# 5_Jetson_Nano_P1.net
KiCad netlist of a schematic drawn in Altium Designer
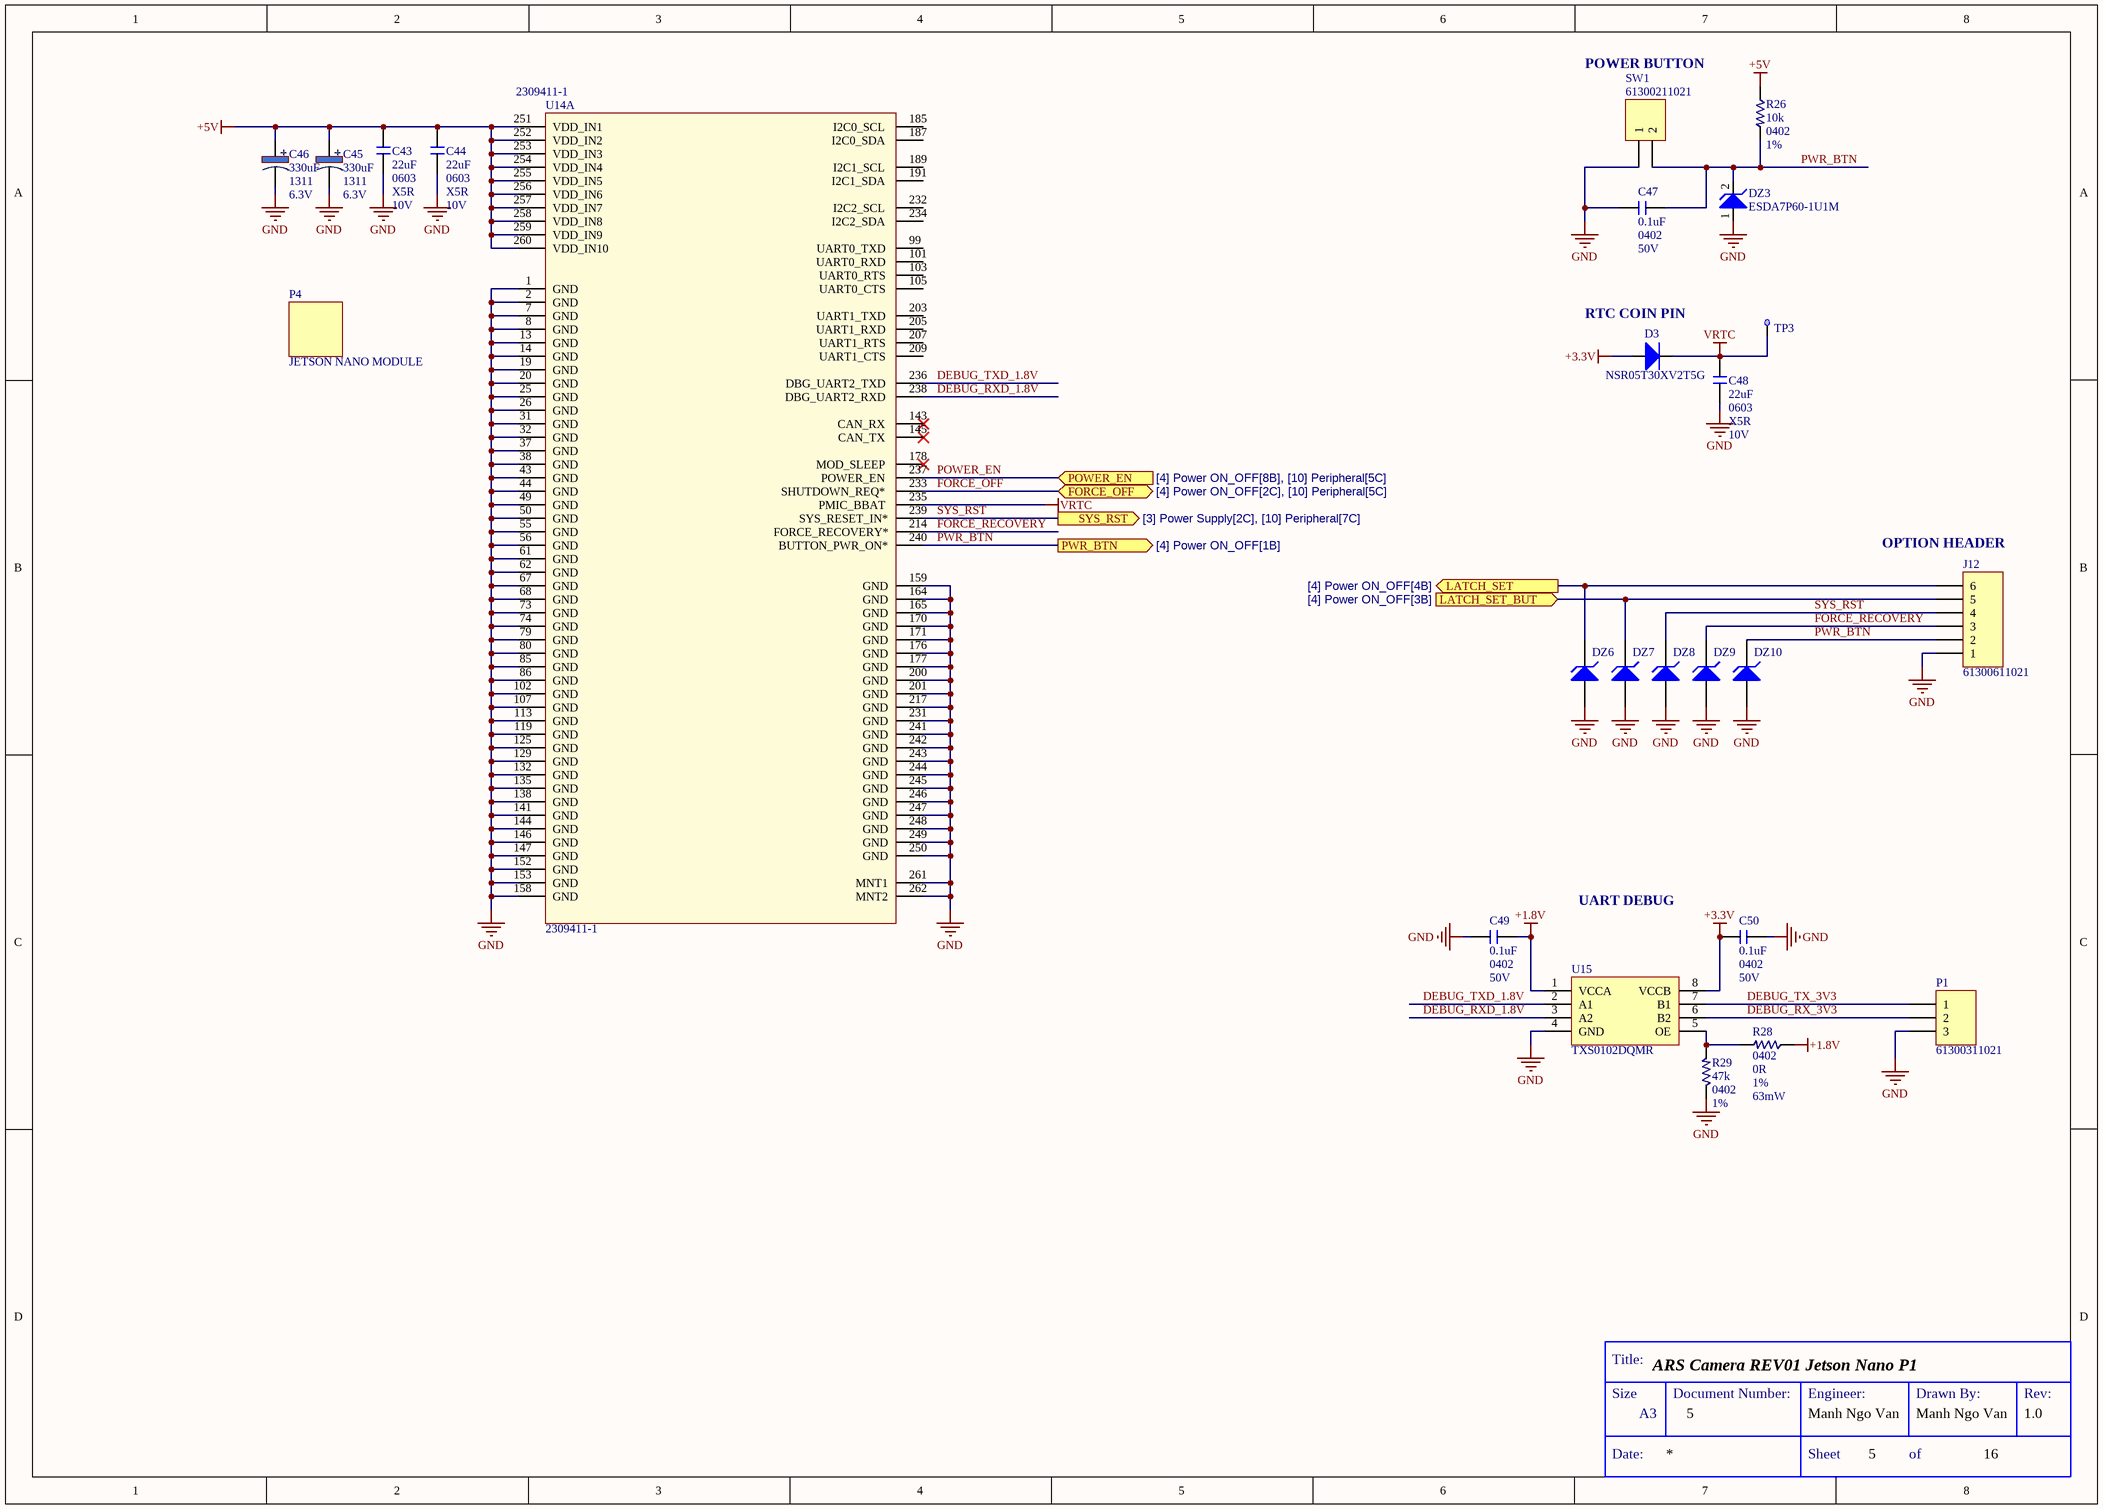
[diagram p0: [5] Jetson Nano P1.SchDoc]

(export (version "E")
  (design (tool "Eeschema 10.0.6"))
  (components
    (comp (ref "C43")
      (value "22uF")
      (footprint "C0603M")
      (description "CAP CER 22UF 10V X5R 0603")
      (fields
        (field (name "MANUFACTURER") "Samsung")
        (field (name "MANUFACTURER PART NUMBER") "CL10A226MP8NUNE")
        (field (name "CASE CODE (IMPERIAL)") "0603")
        (field (name "DIELECTRIC") "X5R")
        (field (name "VOLTAGE RATING") "10V")
      )
      (libsource (lib "CommonLib") (part "CAP_CER"))
    )
    (comp (ref "C44")
      (value "22uF")
      (footprint "C0603M")
      (description "CAP CER 22UF 10V X5R 0603")
      (fields
        (field (name "MANUFACTURER") "Samsung")
        (field (name "MANUFACTURER PART NUMBER") "CL10A226MP8NUNE")
        (field (name "CASE CODE (IMPERIAL)") "0603")
        (field (name "DIELECTRIC") "X5R")
        (field (name "VOLTAGE RATING") "10V")
      )
      (libsource (lib "CommonLib") (part "CAP_CER"))
    )
    (comp (ref "C45")
      (value "330uF")
      (footprint "CP_TANT_3528")
      (description "CAP TANT 330UF 20% 6.3V 1311")
      (fields
        (field (name "MANUFACTURER") "KEMET")
        (field (name "MANUFACTURER PART NUMBER") "T520B337M006ATE070")
        (field (name "CASE/PACKAGE") "1311")
        (field (name "VOLTAGE RATING") "6.3V")
      )
      (libsource (lib "CommonLib") (part "CAP_PL"))
    )
    (comp (ref "C46")
      (value "330uF")
      (footprint "CP_TANT_3528")
      (description "CAP TANT 330UF 20% 6.3V 1311")
      (fields
        (field (name "MANUFACTURER") "KEMET")
        (field (name "MANUFACTURER PART NUMBER") "T520B337M006ATE070")
        (field (name "CASE/PACKAGE") "1311")
        (field (name "VOLTAGE RATING") "6.3V")
      )
      (libsource (lib "CommonLib") (part "CAP_PL"))
    )
    (comp (ref "C47")
      (value "0.1uF")
      (footprint "C0402M")
      (description "CAP CER 0.1UF 50V X7R 0402")
      (fields
        (field (name "MANUFACTURER") "Murata")
        (field (name "MANUFACTURER PART NUMBER") "GRM155R71H104KE14D")
        (field (name "CASE/PACKAGE") "0402")
        (field (name "VOLTAGE") "50V")
      )
      (libsource (lib "CommonLib") (part "CAP_CER"))
    )
    (comp (ref "C48")
      (value "22uF")
      (footprint "C0603M")
      (description "CAP CER 22UF 10V X5R 0603")
      (fields
        (field (name "MANUFACTURER") "Samsung")
        (field (name "MANUFACTURER PART NUMBER") "CL10A226MP8NUNE")
        (field (name "CASE CODE (IMPERIAL)") "0603")
        (field (name "DIELECTRIC") "X5R")
        (field (name "VOLTAGE RATING") "10V")
      )
      (libsource (lib "CommonLib") (part "CAP_CER"))
    )
    (comp (ref "C49")
      (value "0.1uF")
      (footprint "C0402M")
      (description "CAP CER 0.1UF 50V X7R 0402")
      (fields
        (field (name "MANUFACTURER") "Murata")
        (field (name "MANUFACTURER PART NUMBER") "GRM155R71H104KE14D")
        (field (name "CASE/PACKAGE") "0402")
        (field (name "VOLTAGE") "50V")
      )
      (libsource (lib "CommonLib") (part "CAP_CER"))
    )
    (comp (ref "C50")
      (value "0.1uF")
      (footprint "C0402M")
      (description "CAP CER 0.1UF 50V X7R 0402")
      (fields
        (field (name "MANUFACTURER") "Murata")
        (field (name "MANUFACTURER PART NUMBER") "GRM155R71H104KE14D")
        (field (name "CASE/PACKAGE") "0402")
        (field (name "VOLTAGE") "50V")
      )
      (libsource (lib "CommonLib") (part "CAP_CER"))
    )
    (comp (ref "D3")
      (value "NSR05T30XV2T5G")
      (footprint "SODFL160X70-2N")
      (description "DIODE SCHOTTKY 30V 500MA SOD523")
      (fields (field (name "MANUFACTURER") "ON Semiconductor"))
      (libsource (lib "Altium_Library") (part "Diode"))
    )
    (comp (ref "DZ3")
      (value "ESDA7P60-1U1M")
      (footprint "DFN105P160X60-2N")
      (description "TVS DIODE 5V 11.6V 1610")
      (fields (field (name "MANUFACTURER") "STMicroelectronics"))
      (libsource (lib "Ikalogic_MotherBoard") (part "ESDA7P60-1U1M"))
    )
    (comp (ref "DZ6")
      (value "TPD1E10B06DPYR")
      (footprint "R0402M")
      (description "TVS DIODE 5.5V 14V 2X1SON")
      (fields (field (name "MANUFACTURER") "Texas Instruments"))
      (libsource (lib "CommonLib") (part "D Zener"))
    )
    (comp (ref "DZ7")
      (value "TPD1E10B06DPYR")
      (footprint "R0402M")
      (description "TVS DIODE 5.5V 14V 2X1SON")
      (fields (field (name "MANUFACTURER") "Texas Instruments"))
      (libsource (lib "CommonLib") (part "D Zener"))
    )
    (comp (ref "DZ8")
      (value "TPD1E10B06DPYR")
      (footprint "R0402M")
      (description "TVS DIODE 5.5V 14V 2X1SON")
      (fields (field (name "MANUFACTURER") "Texas Instruments"))
      (libsource (lib "CommonLib") (part "D Zener"))
    )
    (comp (ref "DZ9")
      (value "TPD1E10B06DPYR")
      (footprint "R0402M")
      (description "TVS DIODE 5.5V 14V 2X1SON")
      (fields (field (name "MANUFACTURER") "Texas Instruments"))
      (libsource (lib "CommonLib") (part "D Zener"))
    )
    (comp (ref "DZ10")
      (value "TPD1E10B06DPYR")
      (footprint "R0402M")
      (description "TVS DIODE 5.5V 14V 2X1SON")
      (fields (field (name "MANUFACTURER") "Texas Instruments"))
      (libsource (lib "CommonLib") (part "D Zener"))
    )
    (comp (ref "J12")
      (value "61300611021")
      (footprint "HDR1X6")
      (description "CONN HEADER R/A 6POS 2.54MM")
      (fields (field (name "MANUFACTURER") "Würth Elektronik GmbH"))
      (libsource (lib "3DAS_4Camera") (part "Header 6"))
    )
    (comp (ref "P1")
      (value "61300311021")
      (footprint "HDR1X3")
      (description "CONN HEADER R/A 3POS 2.54MM")
      (fields (field (name "MANUFACTURER") "Würth Elektronik GmbH"))
      (libsource (lib "Miscellaneous Connectors") (part "Header 3"))
    )
    (comp (ref "P4") (value "JETSON NANO MODULE") (libsource (lib "CommonLib") (part "ADDITION")))
    (comp (ref "R26")
      (value "10k")
      (footprint "R0402M")
      (description "RES SMD 10K OHM 1% 1/16W 0402")
      (fields
        (field (name "MANUFACTURER") "Yageo")
        (field (name "MANUFACTURER PART NUMBER") "RC0402FR-0710KL")
        (field (name "CASE CODE (IMPERIAL)") "0402")
        (field (name "TOLERANCE") "1%")
      )
      (libsource (lib "CommonLib") (part "RES_SMD"))
    )
    (comp (ref "R28")
      (value "RC0402FR-070RL")
      (footprint "R0402M")
      (description "RC Series 0402 0.063 W 0 Ohm Jumper Surface Mount Thick Film Chip Resistor")
      (fields
        (field (name "CASE CODE (IMPERIAL)") "0402")
        (field (name "RESISTANCE") "0R")
        (field (name "TOLERANCE") "1%")
        (field (name "MAX POWER DISSIPATION") "63mW")
      )
      (libsource (lib "CommonLib") (part "RES_SMD"))
    )
    (comp (ref "R29")
      (value "47k")
      (footprint "R0402M")
      (description "RES SMD 47K OHM 1% 1/16W 0402")
      (fields
        (field (name "MANUFACTURER") "Yageo")
        (field (name "MANUFACTURER PART NUMBER") "RC0402FR-0747KL")
        (field (name "CASE CODE (IMPERIAL)") "0402")
        (field (name "TOLERANCE") "1%")
      )
      (libsource (lib "CommonLib") (part "RES_SMD"))
    )
    (comp (ref "SW1")
      (value "61300211021")
      (footprint "HDR1X2")
      (description "CONN HEADER R/A 2POS 2.54MM")
      (fields (field (name "MANUFACTURER") "Würth Elektronik GmbH"))
      (libsource (lib "Miscellaneous Connectors") (part "Header 2"))
    )
    (comp (ref "TP3")
      (value "TP")
      (footprint "Test point")
      (description "TESTPOINT")
      (libsource (lib "CommonLib") (part "TestPoint"))
    )
    (comp (ref "U14")
      (value "2309411-1")
      (footprint "2309411-1")
      (description "DDR4 SODIMM 260P 8.0H STD")
      (fields
        (field (name "MANUFACTURER") "TE Connectivity")
        (field (name "SUPPLIER PART NUMBER 1") "2309411-1")
      )
      (libsource (lib "Nauvus") (part "Jetson Nano SODIMM"))
    )
    (comp (ref "U15")
      (value "TXS0102DQMR")
      (footprint "SON35P100X40-8N")
      (description "IC TRNSLTR BIDIRECTIONAL 8X2SON")
      (fields (field (name "MANUFACTURER") "Texas Instruments"))
      (libsource (lib "Nauvus") (part "TXS0102DQMR"))
    )
  )
  (nets
    (net (code "1") (name "+1.8V") (class "Default")
      (node (ref "C49") (pin "2") (pinfunction "2_2") (pintype "passive"))
      (node (ref "R28") (pin "2") (pinfunction "2_2") (pintype "passive"))
      (node (ref "U15") (pin "1") (pinfunction "VCCA_1") (pintype "passive"))
    )
    (net (code "2") (name "+3.3V") (class "Default")
      (node (ref "C50") (pin "2") (pinfunction "2_2") (pintype "passive"))
      (node (ref "D3") (pin "2") (pinfunction "A_2") (pintype "passive"))
      (node (ref "U15") (pin "8") (pinfunction "VCCB_8") (pintype "passive"))
    )
    (net (code "3") (name "+5V") (class "Default")
      (node (ref "C43") (pin "2") (pinfunction "2_2") (pintype "passive"))
      (node (ref "C44") (pin "2") (pinfunction "2_2") (pintype "passive"))
      (node (ref "C45") (pin "1") (pinfunction "1_1") (pintype "passive"))
      (node (ref "C46") (pin "1") (pinfunction "1_1") (pintype "passive"))
      (node (ref "R26") (pin "2") (pinfunction "2_2") (pintype "passive"))
      (node (ref "U14") (pin "251") (pinfunction "VDD_IN1_251") (pintype "passive"))
      (node (ref "U14") (pin "252") (pinfunction "VDD_IN2_252") (pintype "passive"))
      (node (ref "U14") (pin "253") (pinfunction "VDD_IN3_253") (pintype "passive"))
      (node (ref "U14") (pin "254") (pinfunction "VDD_IN4_254") (pintype "passive"))
      (node (ref "U14") (pin "255") (pinfunction "VDD_IN5_255") (pintype "passive"))
      (node (ref "U14") (pin "256") (pinfunction "VDD_IN6_256") (pintype "passive"))
      (node (ref "U14") (pin "257") (pinfunction "VDD_IN7_257") (pintype "passive"))
      (node (ref "U14") (pin "258") (pinfunction "VDD_IN8_258") (pintype "passive"))
      (node (ref "U14") (pin "259") (pinfunction "VDD_IN9_259") (pintype "passive"))
      (node (ref "U14") (pin "260") (pinfunction "VDD_IN10_260") (pintype "passive"))
    )
    (net (code "4") (name "/DEBUG_RXD_1.8V") (class "Default")
      (node (ref "U14") (pin "238") (pinfunction "DBG_UART2_RXD_238") (pintype "passive"))
      (node (ref "U15") (pin "3") (pinfunction "A2_3") (pintype "passive"))
    )
    (net (code "5") (name "/DEBUG_RX_3V3") (class "Default")
      (node (ref "P1") (pin "2") (pinfunction "2_2") (pintype "passive"))
      (node (ref "U15") (pin "6") (pinfunction "B2_6") (pintype "passive"))
    )
    (net (code "6") (name "/DEBUG_TXD_1.8V") (class "Default")
      (node (ref "U14") (pin "236") (pinfunction "DBG_UART2_TXD_236") (pintype "passive"))
      (node (ref "U15") (pin "2") (pinfunction "A1_2") (pintype "passive"))
    )
    (net (code "7") (name "/DEBUG_TX_3V3") (class "Default")
      (node (ref "P1") (pin "1") (pinfunction "1_1") (pintype "passive"))
      (node (ref "U15") (pin "7") (pinfunction "B1_7") (pintype "passive"))
    )
    (net (code "8") (name "/FORCE_OFF") (class "Default")
      (node (ref "U14") (pin "233") (pinfunction "SHUTDOWN_REQ*_233") (pintype "passive"))
    )
    (net (code "9") (name "/FORCE_RECOVERY") (class "Default")
      (node (ref "DZ9") (pin "2") (pinfunction "K_2") (pintype "passive"))
      (node (ref "J12") (pin "3") (pinfunction "3_3") (pintype "passive"))
      (node (ref "U14") (pin "214") (pinfunction "FORCE_RECOVERY*_214") (pintype "passive"))
    )
    (net (code "10") (name "/LATCH_SET") (class "Default")
      (node (ref "DZ6") (pin "2") (pinfunction "K_2") (pintype "passive"))
      (node (ref "J12") (pin "6") (pinfunction "6_6") (pintype "passive"))
    )
    (net (code "11") (name "/LATCH_SET_BUT") (class "Default")
      (node (ref "DZ7") (pin "2") (pinfunction "K_2") (pintype "passive"))
      (node (ref "J12") (pin "5") (pinfunction "5_5") (pintype "passive"))
    )
    (net (code "12") (name "/POWER_EN") (class "Default")
      (node (ref "U14") (pin "237") (pinfunction "POWER_EN_237") (pintype "passive"))
    )
    (net (code "13") (name "/PWR_BTN") (class "Default")
      (node (ref "C47") (pin "1") (pinfunction "1_1") (pintype "passive"))
      (node (ref "DZ10") (pin "2") (pinfunction "K_2") (pintype "passive"))
      (node (ref "DZ3") (pin "2") (pinfunction "K_2") (pintype "passive"))
      (node (ref "J12") (pin "2") (pinfunction "2_2") (pintype "passive"))
      (node (ref "R26") (pin "1") (pinfunction "1_1") (pintype "passive"))
      (node (ref "SW1") (pin "2") (pinfunction "2_2") (pintype "passive"))
      (node (ref "U14") (pin "240") (pinfunction "BUTTON_PWR_ON*_240") (pintype "passive"))
    )
    (net (code "14") (name "/SYS_RST") (class "Default")
      (node (ref "DZ8") (pin "2") (pinfunction "K_2") (pintype "passive"))
      (node (ref "J12") (pin "4") (pinfunction "4_4") (pintype "passive"))
      (node (ref "U14") (pin "239") (pinfunction "SYS_RESET_IN*_239") (pintype "passive"))
    )
    (net (code "15") (name "GND") (class "Default")
      (node (ref "C43") (pin "1") (pinfunction "1_1") (pintype "passive"))
      (node (ref "C44") (pin "1") (pinfunction "1_1") (pintype "passive"))
      (node (ref "C45") (pin "2") (pinfunction "2_2") (pintype "passive"))
      (node (ref "C46") (pin "2") (pinfunction "2_2") (pintype "passive"))
      (node (ref "C47") (pin "2") (pinfunction "2_2") (pintype "passive"))
      (node (ref "C48") (pin "1") (pinfunction "1_1") (pintype "passive"))
      (node (ref "C49") (pin "1") (pinfunction "1_1") (pintype "passive"))
      (node (ref "C50") (pin "1") (pinfunction "1_1") (pintype "passive"))
      (node (ref "DZ10") (pin "1") (pinfunction "A_1") (pintype "passive"))
      (node (ref "DZ3") (pin "1") (pinfunction "A_1") (pintype "passive"))
      (node (ref "DZ6") (pin "1") (pinfunction "A_1") (pintype "passive"))
      (node (ref "DZ7") (pin "1") (pinfunction "A_1") (pintype "passive"))
      (node (ref "DZ8") (pin "1") (pinfunction "A_1") (pintype "passive"))
      (node (ref "DZ9") (pin "1") (pinfunction "A_1") (pintype "passive"))
      (node (ref "J12") (pin "1") (pinfunction "1_1") (pintype "passive"))
      (node (ref "P1") (pin "3") (pinfunction "3_3") (pintype "passive"))
      (node (ref "R29") (pin "2") (pinfunction "2_2") (pintype "passive"))
      (node (ref "SW1") (pin "1") (pinfunction "1_1") (pintype "passive"))
      (node (ref "U14") (pin "1") (pinfunction "GND_1") (pintype "passive"))
      (node (ref "U14") (pin "102") (pinfunction "GND_102") (pintype "passive"))
      (node (ref "U14") (pin "107") (pinfunction "GND_107") (pintype "passive"))
      (node (ref "U14") (pin "113") (pinfunction "GND_113") (pintype "passive"))
      (node (ref "U14") (pin "119") (pinfunction "GND_119") (pintype "passive"))
      (node (ref "U14") (pin "125") (pinfunction "GND_125") (pintype "passive"))
      (node (ref "U14") (pin "129") (pinfunction "GND_129") (pintype "passive"))
      (node (ref "U14") (pin "13") (pinfunction "GND_13") (pintype "passive"))
      (node (ref "U14") (pin "132") (pinfunction "GND_132") (pintype "passive"))
      (node (ref "U14") (pin "135") (pinfunction "GND_135") (pintype "passive"))
      (node (ref "U14") (pin "138") (pinfunction "GND_138") (pintype "passive"))
      (node (ref "U14") (pin "14") (pinfunction "GND_14") (pintype "passive"))
      (node (ref "U14") (pin "141") (pinfunction "GND_141") (pintype "passive"))
      (node (ref "U14") (pin "144") (pinfunction "GND_144") (pintype "passive"))
      (node (ref "U14") (pin "146") (pinfunction "GND_146") (pintype "passive"))
      (node (ref "U14") (pin "147") (pinfunction "GND_147") (pintype "passive"))
      (node (ref "U14") (pin "152") (pinfunction "GND_152") (pintype "passive"))
      (node (ref "U14") (pin "153") (pinfunction "GND_153") (pintype "passive"))
      (node (ref "U14") (pin "158") (pinfunction "GND_158") (pintype "passive"))
      (node (ref "U14") (pin "159") (pinfunction "GND_159") (pintype "passive"))
      (node (ref "U14") (pin "164") (pinfunction "GND_164") (pintype "passive"))
      (node (ref "U14") (pin "165") (pinfunction "GND_165") (pintype "passive"))
      (node (ref "U14") (pin "170") (pinfunction "GND_170") (pintype "passive"))
      (node (ref "U14") (pin "171") (pinfunction "GND_171") (pintype "passive"))
      (node (ref "U14") (pin "176") (pinfunction "GND_176") (pintype "passive"))
      (node (ref "U14") (pin "177") (pinfunction "GND_177") (pintype "passive"))
      (node (ref "U14") (pin "19") (pinfunction "GND_19") (pintype "passive"))
      (node (ref "U14") (pin "2") (pinfunction "GND_2") (pintype "passive"))
      (node (ref "U14") (pin "20") (pinfunction "GND_20") (pintype "passive"))
      (node (ref "U14") (pin "200") (pinfunction "GND_200") (pintype "passive"))
      (node (ref "U14") (pin "201") (pinfunction "GND_201") (pintype "passive"))
      (node (ref "U14") (pin "217") (pinfunction "GND_217") (pintype "passive"))
      (node (ref "U14") (pin "231") (pinfunction "GND_231") (pintype "passive"))
      (node (ref "U14") (pin "241") (pinfunction "GND_241") (pintype "passive"))
      (node (ref "U14") (pin "242") (pinfunction "GND_242") (pintype "passive"))
      (node (ref "U14") (pin "243") (pinfunction "GND_243") (pintype "passive"))
      (node (ref "U14") (pin "244") (pinfunction "GND_244") (pintype "passive"))
      (node (ref "U14") (pin "245") (pinfunction "GND_245") (pintype "passive"))
      (node (ref "U14") (pin "246") (pinfunction "GND_246") (pintype "passive"))
      (node (ref "U14") (pin "247") (pinfunction "GND_247") (pintype "passive"))
      (node (ref "U14") (pin "248") (pinfunction "GND_248") (pintype "passive"))
      (node (ref "U14") (pin "249") (pinfunction "GND_249") (pintype "passive"))
      (node (ref "U14") (pin "25") (pinfunction "GND_25") (pintype "passive"))
      (node (ref "U14") (pin "250") (pinfunction "GND_250") (pintype "passive"))
      (node (ref "U14") (pin "26") (pinfunction "GND_26") (pintype "passive"))
      (node (ref "U14") (pin "261") (pinfunction "MNT1_261") (pintype "passive"))
      (node (ref "U14") (pin "262") (pinfunction "MNT2_262") (pintype "passive"))
      (node (ref "U14") (pin "31") (pinfunction "GND_31") (pintype "passive"))
      (node (ref "U14") (pin "32") (pinfunction "GND_32") (pintype "passive"))
      (node (ref "U14") (pin "37") (pinfunction "GND_37") (pintype "passive"))
      (node (ref "U14") (pin "38") (pinfunction "GND_38") (pintype "passive"))
      (node (ref "U14") (pin "43") (pinfunction "GND_43") (pintype "passive"))
      (node (ref "U14") (pin "44") (pinfunction "GND_44") (pintype "passive"))
      (node (ref "U14") (pin "49") (pinfunction "GND_49") (pintype "passive"))
      (node (ref "U14") (pin "50") (pinfunction "GND_50") (pintype "passive"))
      (node (ref "U14") (pin "55") (pinfunction "GND_55") (pintype "passive"))
      (node (ref "U14") (pin "56") (pinfunction "GND_56") (pintype "passive"))
      (node (ref "U14") (pin "61") (pinfunction "GND_61") (pintype "passive"))
      (node (ref "U14") (pin "62") (pinfunction "GND_62") (pintype "passive"))
      (node (ref "U14") (pin "67") (pinfunction "GND_67") (pintype "passive"))
      (node (ref "U14") (pin "68") (pinfunction "GND_68") (pintype "passive"))
      (node (ref "U14") (pin "7") (pinfunction "GND_7") (pintype "passive"))
      (node (ref "U14") (pin "73") (pinfunction "GND_73") (pintype "passive"))
      (node (ref "U14") (pin "74") (pinfunction "GND_74") (pintype "passive"))
      (node (ref "U14") (pin "79") (pinfunction "GND_79") (pintype "passive"))
      (node (ref "U14") (pin "8") (pinfunction "GND_8") (pintype "passive"))
      (node (ref "U14") (pin "80") (pinfunction "GND_80") (pintype "passive"))
      (node (ref "U14") (pin "85") (pinfunction "GND_85") (pintype "passive"))
      (node (ref "U14") (pin "86") (pinfunction "GND_86") (pintype "passive"))
      (node (ref "U15") (pin "4") (pinfunction "GND_4") (pintype "passive"))
    )
    (net (code "16") (name "Net-(U15-OE)") (class "Default")
      (node (ref "R28") (pin "1") (pinfunction "1_1") (pintype "passive"))
      (node (ref "R29") (pin "1") (pinfunction "1_1") (pintype "passive"))
      (node (ref "U15") (pin "5") (pinfunction "OE_5") (pintype "passive"))
    )
    (net (code "17") (name "VRTC") (class "Default")
      (node (ref "C48") (pin "2") (pinfunction "2_2") (pintype "passive"))
      (node (ref "D3") (pin "1") (pinfunction "C_1") (pintype "passive"))
      (node (ref "TP3") (pin "1") (pinfunction "TP_1") (pintype "passive"))
      (node (ref "U14") (pin "235") (pinfunction "PMIC_BBAT_235") (pintype "passive"))
    )
    (net (code "18") (name "unconnected-(U14A-CAN_RX-Pad143)") (class "Default")
      (node (ref "U14") (pin "143") (pinfunction "CAN_RX_143") (pintype "passive+no_connect"))
    )
    (net (code "19") (name "unconnected-(U14A-CAN_TX-Pad145)") (class "Default")
      (node (ref "U14") (pin "145") (pinfunction "CAN_TX_145") (pintype "passive+no_connect"))
    )
    (net (code "20") (name "unconnected-(U14A-I2C0_SCL-Pad185)") (class "Default")
      (node (ref "U14") (pin "185") (pinfunction "I2C0_SCL_185") (pintype "passive"))
    )
    (net (code "21") (name "unconnected-(U14A-I2C0_SDA-Pad187)") (class "Default")
      (node (ref "U14") (pin "187") (pinfunction "I2C0_SDA_187") (pintype "passive"))
    )
    (net (code "22") (name "unconnected-(U14A-I2C1_SCL-Pad189)") (class "Default")
      (node (ref "U14") (pin "189") (pinfunction "I2C1_SCL_189") (pintype "passive"))
    )
    (net (code "23") (name "unconnected-(U14A-I2C1_SDA-Pad191)") (class "Default")
      (node (ref "U14") (pin "191") (pinfunction "I2C1_SDA_191") (pintype "passive"))
    )
    (net (code "24") (name "unconnected-(U14A-I2C2_SCL-Pad232)") (class "Default")
      (node (ref "U14") (pin "232") (pinfunction "I2C2_SCL_232") (pintype "passive"))
    )
    (net (code "25") (name "unconnected-(U14A-I2C2_SDA-Pad234)") (class "Default")
      (node (ref "U14") (pin "234") (pinfunction "I2C2_SDA_234") (pintype "passive"))
    )
    (net (code "26") (name "unconnected-(U14A-MOD_SLEEP-Pad178)") (class "Default")
      (node (ref "U14") (pin "178") (pinfunction "MOD_SLEEP_178") (pintype "passive+no_connect"))
    )
    (net (code "27") (name "unconnected-(U14A-UART0_CTS-Pad105)") (class "Default")
      (node (ref "U14") (pin "105") (pinfunction "UART0_CTS_105") (pintype "passive"))
    )
    (net (code "28") (name "unconnected-(U14A-UART0_RTS-Pad103)") (class "Default")
      (node (ref "U14") (pin "103") (pinfunction "UART0_RTS_103") (pintype "passive"))
    )
    (net (code "29") (name "unconnected-(U14A-UART0_RXD-Pad101)") (class "Default")
      (node (ref "U14") (pin "101") (pinfunction "UART0_RXD_101") (pintype "passive"))
    )
    (net (code "30") (name "unconnected-(U14A-UART0_TXD-Pad99)") (class "Default")
      (node (ref "U14") (pin "99") (pinfunction "UART0_TXD_99") (pintype "passive"))
    )
    (net (code "31") (name "unconnected-(U14A-UART1_CTS-Pad209)") (class "Default")
      (node (ref "U14") (pin "209") (pinfunction "UART1_CTS_209") (pintype "passive"))
    )
    (net (code "32") (name "unconnected-(U14A-UART1_RTS-Pad207)") (class "Default")
      (node (ref "U14") (pin "207") (pinfunction "UART1_RTS_207") (pintype "passive"))
    )
    (net (code "33") (name "unconnected-(U14A-UART1_RXD-Pad205)") (class "Default")
      (node (ref "U14") (pin "205") (pinfunction "UART1_RXD_205") (pintype "passive"))
    )
    (net (code "34") (name "unconnected-(U14A-UART1_TXD-Pad203)") (class "Default")
      (node (ref "U14") (pin "203") (pinfunction "UART1_TXD_203") (pintype "passive"))
    )
  )
)
